# claudobip-hdmi-cec.net
KiCad netlist of a schematic drawn in EAGLE
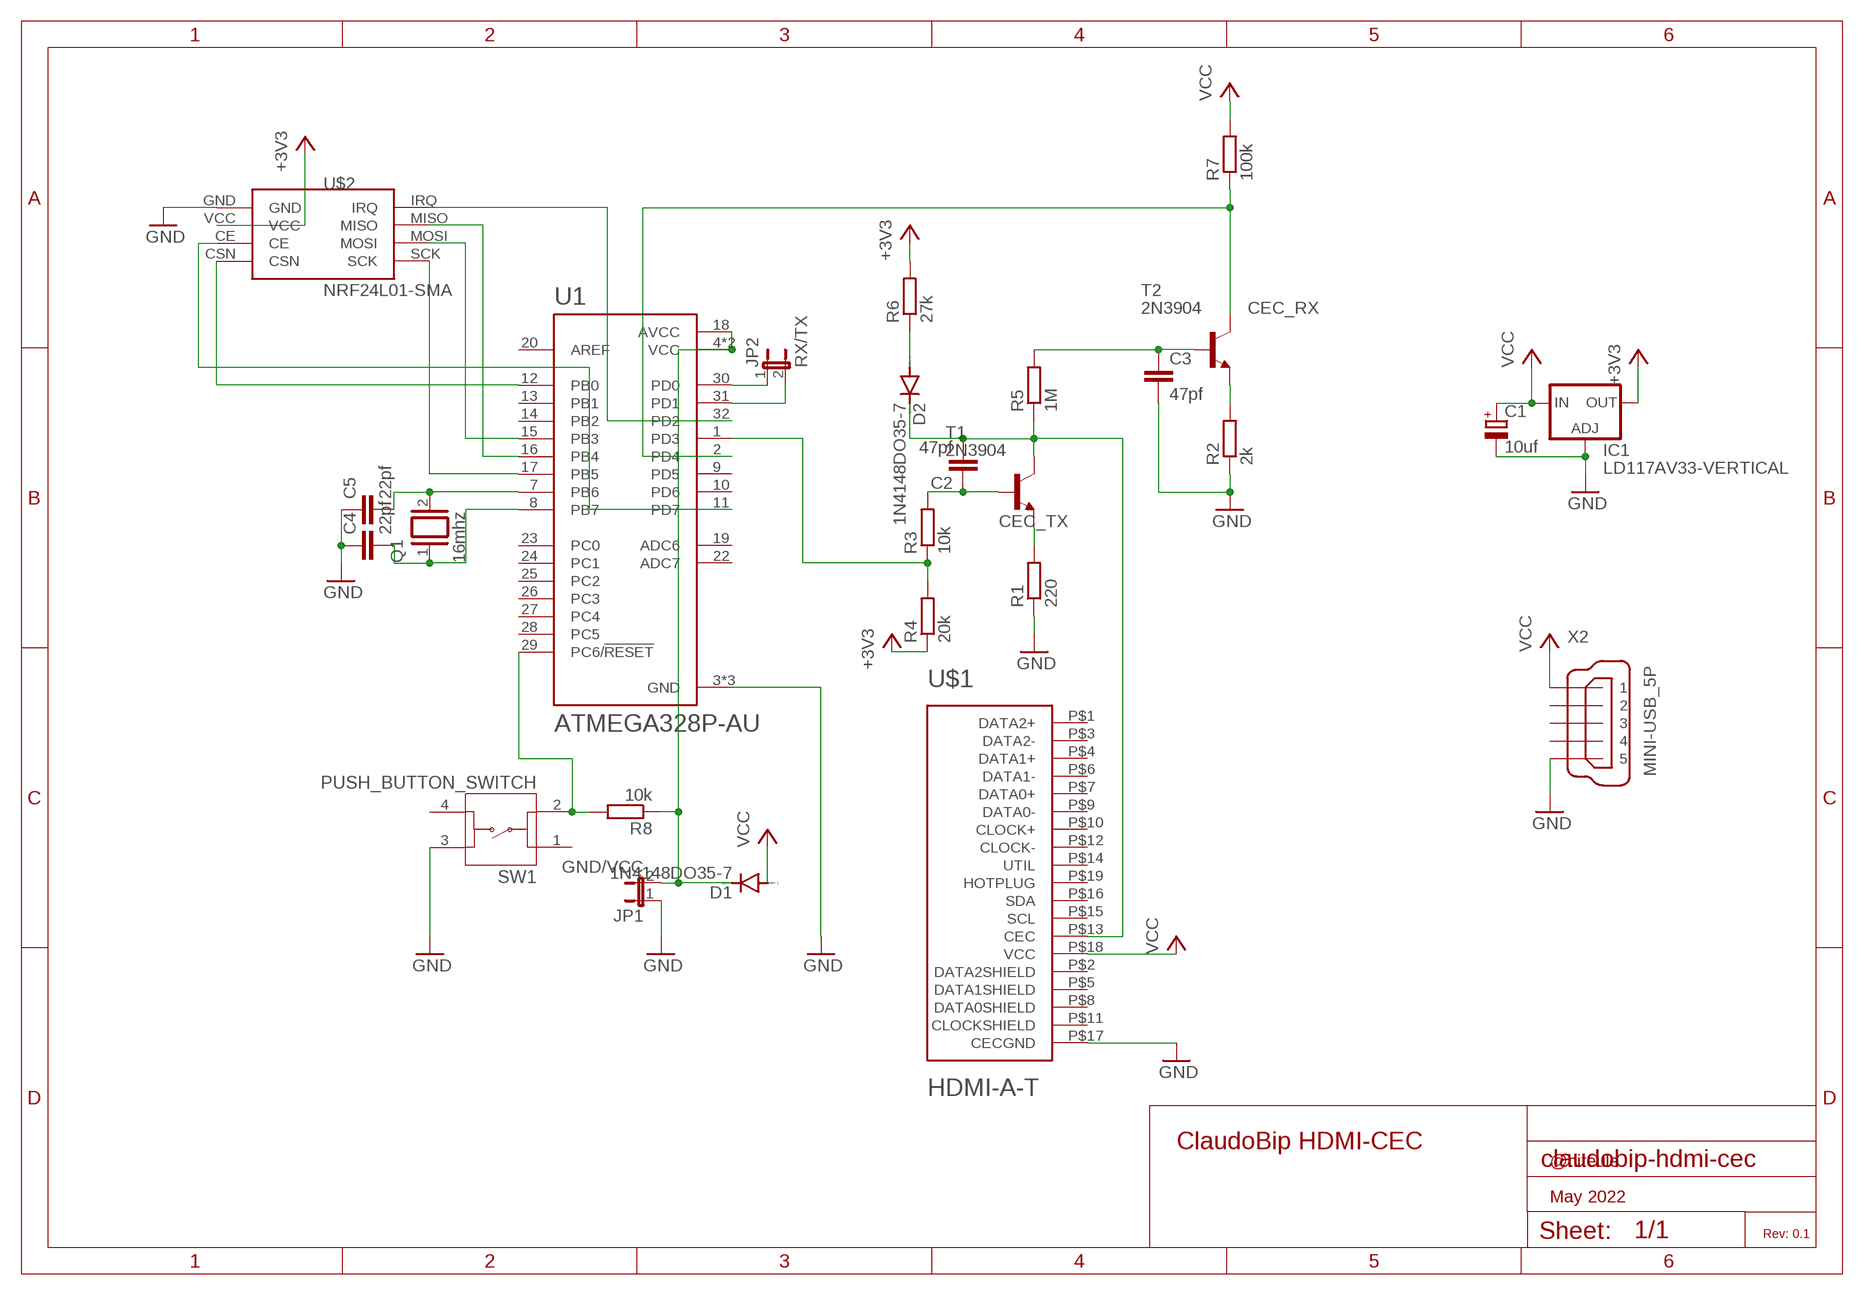
[diagram p0: schematic, sheet 1]

(export (version "E")
  (design (tool "Eeschema 10.0.6"))
  (components
    (comp (ref "C1")
      (value "10uf")
      (footprint "eagle-import:E2,5-6E")
      (libsource (lib "eagle-import") (part "CPOL-EUE2,5-6E"))
    )
    (comp (ref "C2")
      (value "47pf")
      (footprint "eagle-import:C025-024X044")
      (libsource (lib "eagle-import") (part "C-EU025-024X044"))
    )
    (comp (ref "C3")
      (value "47pf")
      (footprint "eagle-import:C025-024X044")
      (libsource (lib "eagle-import") (part "C-EU025-024X044"))
    )
    (comp (ref "C4")
      (value "22pf")
      (footprint "eagle-import:C025-024X044")
      (libsource (lib "eagle-import") (part "C-EU025-024X044"))
    )
    (comp (ref "C5")
      (value "22pf")
      (footprint "eagle-import:C025-024X044")
      (libsource (lib "eagle-import") (part "C-EU025-024X044"))
    )
    (comp (ref "D1")
      (value "1N4148DO35-7")
      (footprint "eagle-import:DO35-7")
      (libsource (lib "eagle-import") (part "1N4148DO35-7"))
    )
    (comp (ref "D2")
      (value "1N4148DO35-7")
      (footprint "eagle-import:DO35-7")
      (libsource (lib "eagle-import") (part "1N4148DO35-7"))
    )
    (comp (ref "IC1")
      (value "LD117AV33-VERTICAL")
      (footprint "eagle-import:TO220S-VERTICAL")
      (libsource (lib "eagle-import") (part "LD117AV33-VERTICAL"))
    )
    (comp (ref "JP1")
      (value "GND/VCC")
      (footprint "eagle-import:JP1")
      (libsource (lib "eagle-import") (part "JP1E"))
    )
    (comp (ref "JP2")
      (value "RX/TX")
      (footprint "eagle-import:JP1")
      (libsource (lib "eagle-import") (part "JP1E"))
    )
    (comp (ref "Q1")
      (value "16mhz")
      (footprint "eagle-import:QS")
      (libsource (lib "eagle-import") (part "XTAL/S"))
    )
    (comp (ref "R1")
      (value "220")
      (footprint "eagle-import:0204_7")
      (libsource (lib "eagle-import") (part "R-EU_0204/7"))
    )
    (comp (ref "R2")
      (value "2k")
      (footprint "eagle-import:0204_7")
      (libsource (lib "eagle-import") (part "R-EU_0204/7"))
    )
    (comp (ref "R3")
      (value "10k")
      (footprint "eagle-import:0204_7")
      (libsource (lib "eagle-import") (part "R-EU_0204/7"))
    )
    (comp (ref "R4")
      (value "20k")
      (footprint "eagle-import:0204_7")
      (libsource (lib "eagle-import") (part "R-EU_0204/7"))
    )
    (comp (ref "R5")
      (value "1M")
      (footprint "eagle-import:0204_7")
      (libsource (lib "eagle-import") (part "R-EU_0204/7"))
    )
    (comp (ref "R6")
      (value "27k")
      (footprint "eagle-import:0204_7")
      (libsource (lib "eagle-import") (part "R-EU_0204/7"))
    )
    (comp (ref "R7")
      (value "100k")
      (footprint "eagle-import:0204_7")
      (libsource (lib "eagle-import") (part "R-EU_0204/7"))
    )
    (comp (ref "R8")
      (value "10k")
      (footprint "eagle-import:0204_7")
      (libsource (lib "eagle-import") (part "R-EU_0204/7"))
    )
    (comp (ref "SW1")
      (value "PUSH_BUTTON_SWITCH")
      (footprint "eagle-import:PUSH_BUTTON_SWITCH")
      (libsource (lib "eagle-import") (part "PUSH_BUTTON_SWITCH"))
    )
    (comp (ref "T1")
      (value "2N3904")
      (footprint "eagle-import:TO92")
      (libsource (lib "eagle-import") (part "2N3904"))
    )
    (comp (ref "T2")
      (value "2N3904")
      (footprint "eagle-import:TO92")
      (libsource (lib "eagle-import") (part "2N3904"))
    )
    (comp (ref "U$1")
      (value "HDMI-A-T")
      (footprint "eagle-import:HDMI_A-T")
      (libsource (lib "eagle-import") (part "HDMI-A-T"))
    )
    (comp (ref "U$2")
      (value "NRF24L01-SMA")
      (footprint "eagle-import:NRF24L01-SMA")
      (libsource (lib "eagle-import") (part "NRF24L01-SMA"))
    )
    (comp (ref "U1")
      (value "ATMEGA328P-AU")
      (footprint "eagle-import:QFP80P900X900X120-32N")
      (fields (field (name "MF") "Microchip Technology"))
      (libsource (lib "eagle-import") (part "ATMEGA328P-AU"))
    )
    (comp (ref "X2")
      (value "MINI-USB_5P")
      (footprint "eagle-import:MINI-USB_5P")
      (libsource (lib "eagle-import") (part "MINI-USB_5P"))
    )
  )
  (nets
    (net (code "1") (name "+3V3") (class "Default")
      (node (ref "IC1") (pin "2") (pinfunction "OUT_2") (pintype "passive"))
      (node (ref "R4") (pin "1") (pinfunction "1_1") (pintype "passive"))
      (node (ref "R6") (pin "2") (pinfunction "2_2") (pintype "passive"))
      (node (ref "U$2") (pin "VCC") (pinfunction "VCC_VCC") (pintype "bidirectional"))
    )
    (net (code "2") (name "/CEC_RX") (class "Default")
      (node (ref "R7") (pin "1") (pinfunction "1_1") (pintype "passive"))
      (node (ref "T2") (pin "1") (pinfunction "C_1") (pintype "passive"))
      (node (ref "U1") (pin "2") (pinfunction "PD4_2") (pintype "bidirectional"))
    )
    (net (code "3") (name "/CEC_TX") (class "Default")
      (node (ref "C2") (pin "1") (pinfunction "1_1") (pintype "passive"))
      (node (ref "R3") (pin "2") (pinfunction "2_2") (pintype "passive"))
      (node (ref "T1") (pin "2") (pinfunction "B_2") (pintype "passive"))
    )
    (net (code "4") (name "GND") (class "Default")
      (node (ref "C1") (pin "-") (pinfunction "-_-") (pintype "passive"))
      (node (ref "C3") (pin "2") (pinfunction "2_2") (pintype "passive"))
      (node (ref "C4") (pin "1") (pinfunction "1_1") (pintype "passive"))
      (node (ref "C5") (pin "1") (pinfunction "1_1") (pintype "passive"))
      (node (ref "IC1") (pin "1") (pinfunction "ADJ_1") (pintype "input"))
      (node (ref "JP1") (pin "1") (pinfunction "1_1") (pintype "passive"))
      (node (ref "R1") (pin "1") (pinfunction "1_1") (pintype "passive"))
      (node (ref "R2") (pin "1") (pinfunction "1_1") (pintype "passive"))
      (node (ref "SW1") (pin "3") (pinfunction "3_3") (pintype "passive"))
      (node (ref "U$1") (pin "P$17") (pinfunction "CECGND_P$17") (pintype "bidirectional"))
      (node (ref "U$2") (pin "GND") (pinfunction "GND_GND") (pintype "bidirectional"))
      (node (ref "U1") (pin "21") (pinfunction "GND_21") (pintype "power_in"))
      (node (ref "U1") (pin "3") (pinfunction "GND_3") (pintype "power_in"))
      (node (ref "U1") (pin "5") (pinfunction "GND_5") (pintype "power_in"))
      (node (ref "X2") (pin "5") (pinfunction "5_5") (pintype "passive"))
    )
    (net (code "5") (name "Net-(D2-PadA)") (class "Default")
      (node (ref "D2") (pin "A") (pinfunction "A_A") (pintype "passive"))
      (node (ref "R6") (pin "1") (pinfunction "1_1") (pintype "passive"))
    )
    (net (code "6") (name "Net-(T1-C)") (class "Default")
      (node (ref "C2") (pin "2") (pinfunction "2_2") (pintype "passive"))
      (node (ref "D2") (pin "C") (pinfunction "C_C") (pintype "passive"))
      (node (ref "R5") (pin "1") (pinfunction "1_1") (pintype "passive"))
      (node (ref "T1") (pin "1") (pinfunction "C_1") (pintype "passive"))
      (node (ref "U$1") (pin "P$13") (pinfunction "CEC_P$13") (pintype "bidirectional"))
    )
    (net (code "7") (name "Net-(T1-E)") (class "Default")
      (node (ref "R1") (pin "2") (pinfunction "2_2") (pintype "passive"))
      (node (ref "T1") (pin "3") (pinfunction "E_3") (pintype "passive"))
    )
    (net (code "8") (name "Net-(T2-B)") (class "Default")
      (node (ref "C3") (pin "1") (pinfunction "1_1") (pintype "passive"))
      (node (ref "R5") (pin "2") (pinfunction "2_2") (pintype "passive"))
      (node (ref "T2") (pin "2") (pinfunction "B_2") (pintype "passive"))
    )
    (net (code "9") (name "Net-(T2-E)") (class "Default")
      (node (ref "R2") (pin "2") (pinfunction "2_2") (pintype "passive"))
      (node (ref "T2") (pin "3") (pinfunction "E_3") (pintype "passive"))
    )
    (net (code "10") (name "Net-(U1-AVCC)") (class "Default")
      (node (ref "D1") (pin "C") (pinfunction "C_C") (pintype "passive"))
      (node (ref "JP1") (pin "2") (pinfunction "2_2") (pintype "passive"))
      (node (ref "R8") (pin "1") (pinfunction "1_1") (pintype "passive"))
      (node (ref "U1") (pin "18") (pinfunction "AVCC_18") (pintype "power_in"))
      (node (ref "U1") (pin "4") (pinfunction "VCC_4") (pintype "power_in"))
      (node (ref "U1") (pin "6") (pinfunction "VCC_6") (pintype "power_in"))
    )
    (net (code "11") (name "Net-(U1-PB0)") (class "Default")
      (node (ref "U$2") (pin "CSN") (pinfunction "CSN_CSN") (pintype "bidirectional"))
      (node (ref "U1") (pin "12") (pinfunction "PB0_12") (pintype "bidirectional"))
    )
    (net (code "12") (name "Net-(U1-PB3)") (class "Default")
      (node (ref "U$2") (pin "MOSI") (pinfunction "MOSI_MOSI") (pintype "bidirectional"))
      (node (ref "U1") (pin "15") (pinfunction "PB3_15") (pintype "bidirectional"))
    )
    (net (code "13") (name "Net-(U1-PB4)") (class "Default")
      (node (ref "U$2") (pin "MISO") (pinfunction "MISO_MISO") (pintype "bidirectional"))
      (node (ref "U1") (pin "16") (pinfunction "PB4_16") (pintype "bidirectional"))
    )
    (net (code "14") (name "Net-(U1-PB5)") (class "Default")
      (node (ref "U$2") (pin "SCK") (pinfunction "SCK_SCK") (pintype "bidirectional"))
      (node (ref "U1") (pin "17") (pinfunction "PB5_17") (pintype "bidirectional"))
    )
    (net (code "15") (name "Net-(U1-PB6)") (class "Default")
      (node (ref "C5") (pin "2") (pinfunction "2_2") (pintype "passive"))
      (node (ref "Q1") (pin "2") (pinfunction "2_2") (pintype "passive"))
      (node (ref "U1") (pin "7") (pinfunction "PB6_7") (pintype "bidirectional"))
    )
    (net (code "16") (name "Net-(U1-PB7)") (class "Default")
      (node (ref "C4") (pin "2") (pinfunction "2_2") (pintype "passive"))
      (node (ref "Q1") (pin "1") (pinfunction "1_1") (pintype "passive"))
      (node (ref "U1") (pin "8") (pinfunction "PB7_8") (pintype "bidirectional"))
    )
    (net (code "17") (name "Net-(U1-PC6{slash}~{RESET})") (class "Default")
      (node (ref "R8") (pin "2") (pinfunction "2_2") (pintype "passive"))
      (node (ref "SW1") (pin "2") (pinfunction "2_2") (pintype "passive"))
      (node (ref "U1") (pin "29") (pinfunction "PC6/~{RESET}_29") (pintype "bidirectional"))
    )
    (net (code "18") (name "Net-(U1-PD0)") (class "Default")
      (node (ref "JP2") (pin "1") (pinfunction "1_1") (pintype "passive"))
      (node (ref "U1") (pin "30") (pinfunction "PD0_30") (pintype "bidirectional"))
    )
    (net (code "19") (name "Net-(U1-PD1)") (class "Default")
      (node (ref "JP2") (pin "2") (pinfunction "2_2") (pintype "passive"))
      (node (ref "U1") (pin "31") (pinfunction "PD1_31") (pintype "bidirectional"))
    )
    (net (code "20") (name "Net-(U1-PD2)") (class "Default")
      (node (ref "U$2") (pin "IRQ") (pinfunction "IRQ_IRQ") (pintype "bidirectional"))
      (node (ref "U1") (pin "32") (pinfunction "PD2_32") (pintype "bidirectional"))
    )
    (net (code "21") (name "Net-(U1-PD3)") (class "Default")
      (node (ref "R3") (pin "1") (pinfunction "1_1") (pintype "passive"))
      (node (ref "R4") (pin "2") (pinfunction "2_2") (pintype "passive"))
      (node (ref "U1") (pin "1") (pinfunction "PD3_1") (pintype "bidirectional"))
    )
    (net (code "22") (name "Net-(U1-PD7)") (class "Default")
      (node (ref "U$2") (pin "CE") (pinfunction "CE_CE") (pintype "bidirectional"))
      (node (ref "U1") (pin "11") (pinfunction "PD7_11") (pintype "bidirectional"))
    )
    (net (code "23") (name "VCC") (class "Default")
      (node (ref "C1") (pin "+") (pinfunction "+_+") (pintype "passive"))
      (node (ref "D1") (pin "A") (pinfunction "A_A") (pintype "passive"))
      (node (ref "IC1") (pin "3") (pinfunction "IN_3") (pintype "input"))
      (node (ref "R7") (pin "2") (pinfunction "2_2") (pintype "passive"))
      (node (ref "U$1") (pin "P$18") (pinfunction "VCC_P$18") (pintype "bidirectional"))
      (node (ref "X2") (pin "1") (pinfunction "1_1") (pintype "passive"))
    )
    (net (code "24") (name "unconnected-(SW1-Pad1)") (class "Default")
      (node (ref "SW1") (pin "1") (pinfunction "1_1") (pintype "passive"))
    )
    (net (code "25") (name "unconnected-(SW1-Pad4)") (class "Default")
      (node (ref "SW1") (pin "4") (pinfunction "4_4") (pintype "passive"))
    )
    (net (code "26") (name "unconnected-(U$1-CLOCK+-PadP$10)") (class "Default")
      (node (ref "U$1") (pin "P$10") (pinfunction "CLOCK+_P$10") (pintype "bidirectional"))
    )
    (net (code "27") (name "unconnected-(U$1-CLOCK--PadP$12)") (class "Default")
      (node (ref "U$1") (pin "P$12") (pinfunction "CLOCK-_P$12") (pintype "bidirectional"))
    )
    (net (code "28") (name "unconnected-(U$1-CLOCKSHIELD-PadP$11)") (class "Default")
      (node (ref "U$1") (pin "P$11") (pinfunction "CLOCKSHIELD_P$11") (pintype "bidirectional"))
    )
    (net (code "29") (name "unconnected-(U$1-DATA0+-PadP$7)") (class "Default")
      (node (ref "U$1") (pin "P$7") (pinfunction "DATA0+_P$7") (pintype "bidirectional"))
    )
    (net (code "30") (name "unconnected-(U$1-DATA0--PadP$9)") (class "Default")
      (node (ref "U$1") (pin "P$9") (pinfunction "DATA0-_P$9") (pintype "bidirectional"))
    )
    (net (code "31") (name "unconnected-(U$1-DATA0SHIELD-PadP$8)") (class "Default")
      (node (ref "U$1") (pin "P$8") (pinfunction "DATA0SHIELD_P$8") (pintype "bidirectional"))
    )
    (net (code "32") (name "unconnected-(U$1-DATA1+-PadP$4)") (class "Default")
      (node (ref "U$1") (pin "P$4") (pinfunction "DATA1+_P$4") (pintype "bidirectional"))
    )
    (net (code "33") (name "unconnected-(U$1-DATA1--PadP$6)") (class "Default")
      (node (ref "U$1") (pin "P$6") (pinfunction "DATA1-_P$6") (pintype "bidirectional"))
    )
    (net (code "34") (name "unconnected-(U$1-DATA1SHIELD-PadP$5)") (class "Default")
      (node (ref "U$1") (pin "P$5") (pinfunction "DATA1SHIELD_P$5") (pintype "bidirectional"))
    )
    (net (code "35") (name "unconnected-(U$1-DATA2+-PadP$1)") (class "Default")
      (node (ref "U$1") (pin "P$1") (pinfunction "DATA2+_P$1") (pintype "bidirectional"))
    )
    (net (code "36") (name "unconnected-(U$1-DATA2--PadP$3)") (class "Default")
      (node (ref "U$1") (pin "P$3") (pinfunction "DATA2-_P$3") (pintype "bidirectional"))
    )
    (net (code "37") (name "unconnected-(U$1-DATA2SHIELD-PadP$2)") (class "Default")
      (node (ref "U$1") (pin "P$2") (pinfunction "DATA2SHIELD_P$2") (pintype "bidirectional"))
    )
    (net (code "38") (name "unconnected-(U$1-HOTPLUG-PadP$19)") (class "Default")
      (node (ref "U$1") (pin "P$19") (pinfunction "HOTPLUG_P$19") (pintype "bidirectional"))
    )
    (net (code "39") (name "unconnected-(U$1-SCL-PadP$15)") (class "Default")
      (node (ref "U$1") (pin "P$15") (pinfunction "SCL_P$15") (pintype "bidirectional"))
    )
    (net (code "40") (name "unconnected-(U$1-SDA-PadP$16)") (class "Default")
      (node (ref "U$1") (pin "P$16") (pinfunction "SDA_P$16") (pintype "bidirectional"))
    )
    (net (code "41") (name "unconnected-(U$1-UTIL-PadP$14)") (class "Default")
      (node (ref "U$1") (pin "P$14") (pinfunction "UTIL_P$14") (pintype "bidirectional"))
    )
    (net (code "42") (name "unconnected-(U1-ADC6-Pad19)") (class "Default")
      (node (ref "U1") (pin "19") (pinfunction "ADC6_19") (pintype "bidirectional"))
    )
    (net (code "43") (name "unconnected-(U1-ADC7-Pad22)") (class "Default")
      (node (ref "U1") (pin "22") (pinfunction "ADC7_22") (pintype "bidirectional"))
    )
    (net (code "44") (name "unconnected-(U1-AREF-Pad20)") (class "Default")
      (node (ref "U1") (pin "20") (pinfunction "AREF_20") (pintype "input"))
    )
    (net (code "45") (name "unconnected-(U1-PB1-Pad13)") (class "Default")
      (node (ref "U1") (pin "13") (pinfunction "PB1_13") (pintype "bidirectional"))
    )
    (net (code "46") (name "unconnected-(U1-PB2-Pad14)") (class "Default")
      (node (ref "U1") (pin "14") (pinfunction "PB2_14") (pintype "bidirectional"))
    )
    (net (code "47") (name "unconnected-(U1-PC0-Pad23)") (class "Default")
      (node (ref "U1") (pin "23") (pinfunction "PC0_23") (pintype "bidirectional"))
    )
    (net (code "48") (name "unconnected-(U1-PC1-Pad24)") (class "Default")
      (node (ref "U1") (pin "24") (pinfunction "PC1_24") (pintype "bidirectional"))
    )
    (net (code "49") (name "unconnected-(U1-PC2-Pad25)") (class "Default")
      (node (ref "U1") (pin "25") (pinfunction "PC2_25") (pintype "bidirectional"))
    )
    (net (code "50") (name "unconnected-(U1-PC3-Pad26)") (class "Default")
      (node (ref "U1") (pin "26") (pinfunction "PC3_26") (pintype "bidirectional"))
    )
    (net (code "51") (name "unconnected-(U1-PC4-Pad27)") (class "Default")
      (node (ref "U1") (pin "27") (pinfunction "PC4_27") (pintype "bidirectional"))
    )
    (net (code "52") (name "unconnected-(U1-PC5-Pad28)") (class "Default")
      (node (ref "U1") (pin "28") (pinfunction "PC5_28") (pintype "bidirectional"))
    )
    (net (code "53") (name "unconnected-(U1-PD5-Pad9)") (class "Default")
      (node (ref "U1") (pin "9") (pinfunction "PD5_9") (pintype "bidirectional"))
    )
    (net (code "54") (name "unconnected-(U1-PD6-Pad10)") (class "Default")
      (node (ref "U1") (pin "10") (pinfunction "PD6_10") (pintype "bidirectional"))
    )
    (net (code "55") (name "unconnected-(X2-Pad2)") (class "Default")
      (node (ref "X2") (pin "2") (pinfunction "2_2") (pintype "passive"))
    )
    (net (code "56") (name "unconnected-(X2-Pad3)") (class "Default")
      (node (ref "X2") (pin "3") (pinfunction "3_3") (pintype "passive"))
    )
    (net (code "57") (name "unconnected-(X2-Pad4)") (class "Default")
      (node (ref "X2") (pin "4") (pinfunction "4_4") (pintype "passive"))
    )
  )
)
